# EnsembleNine.net
KiCad netlist of a schematic drawn in EAGLE
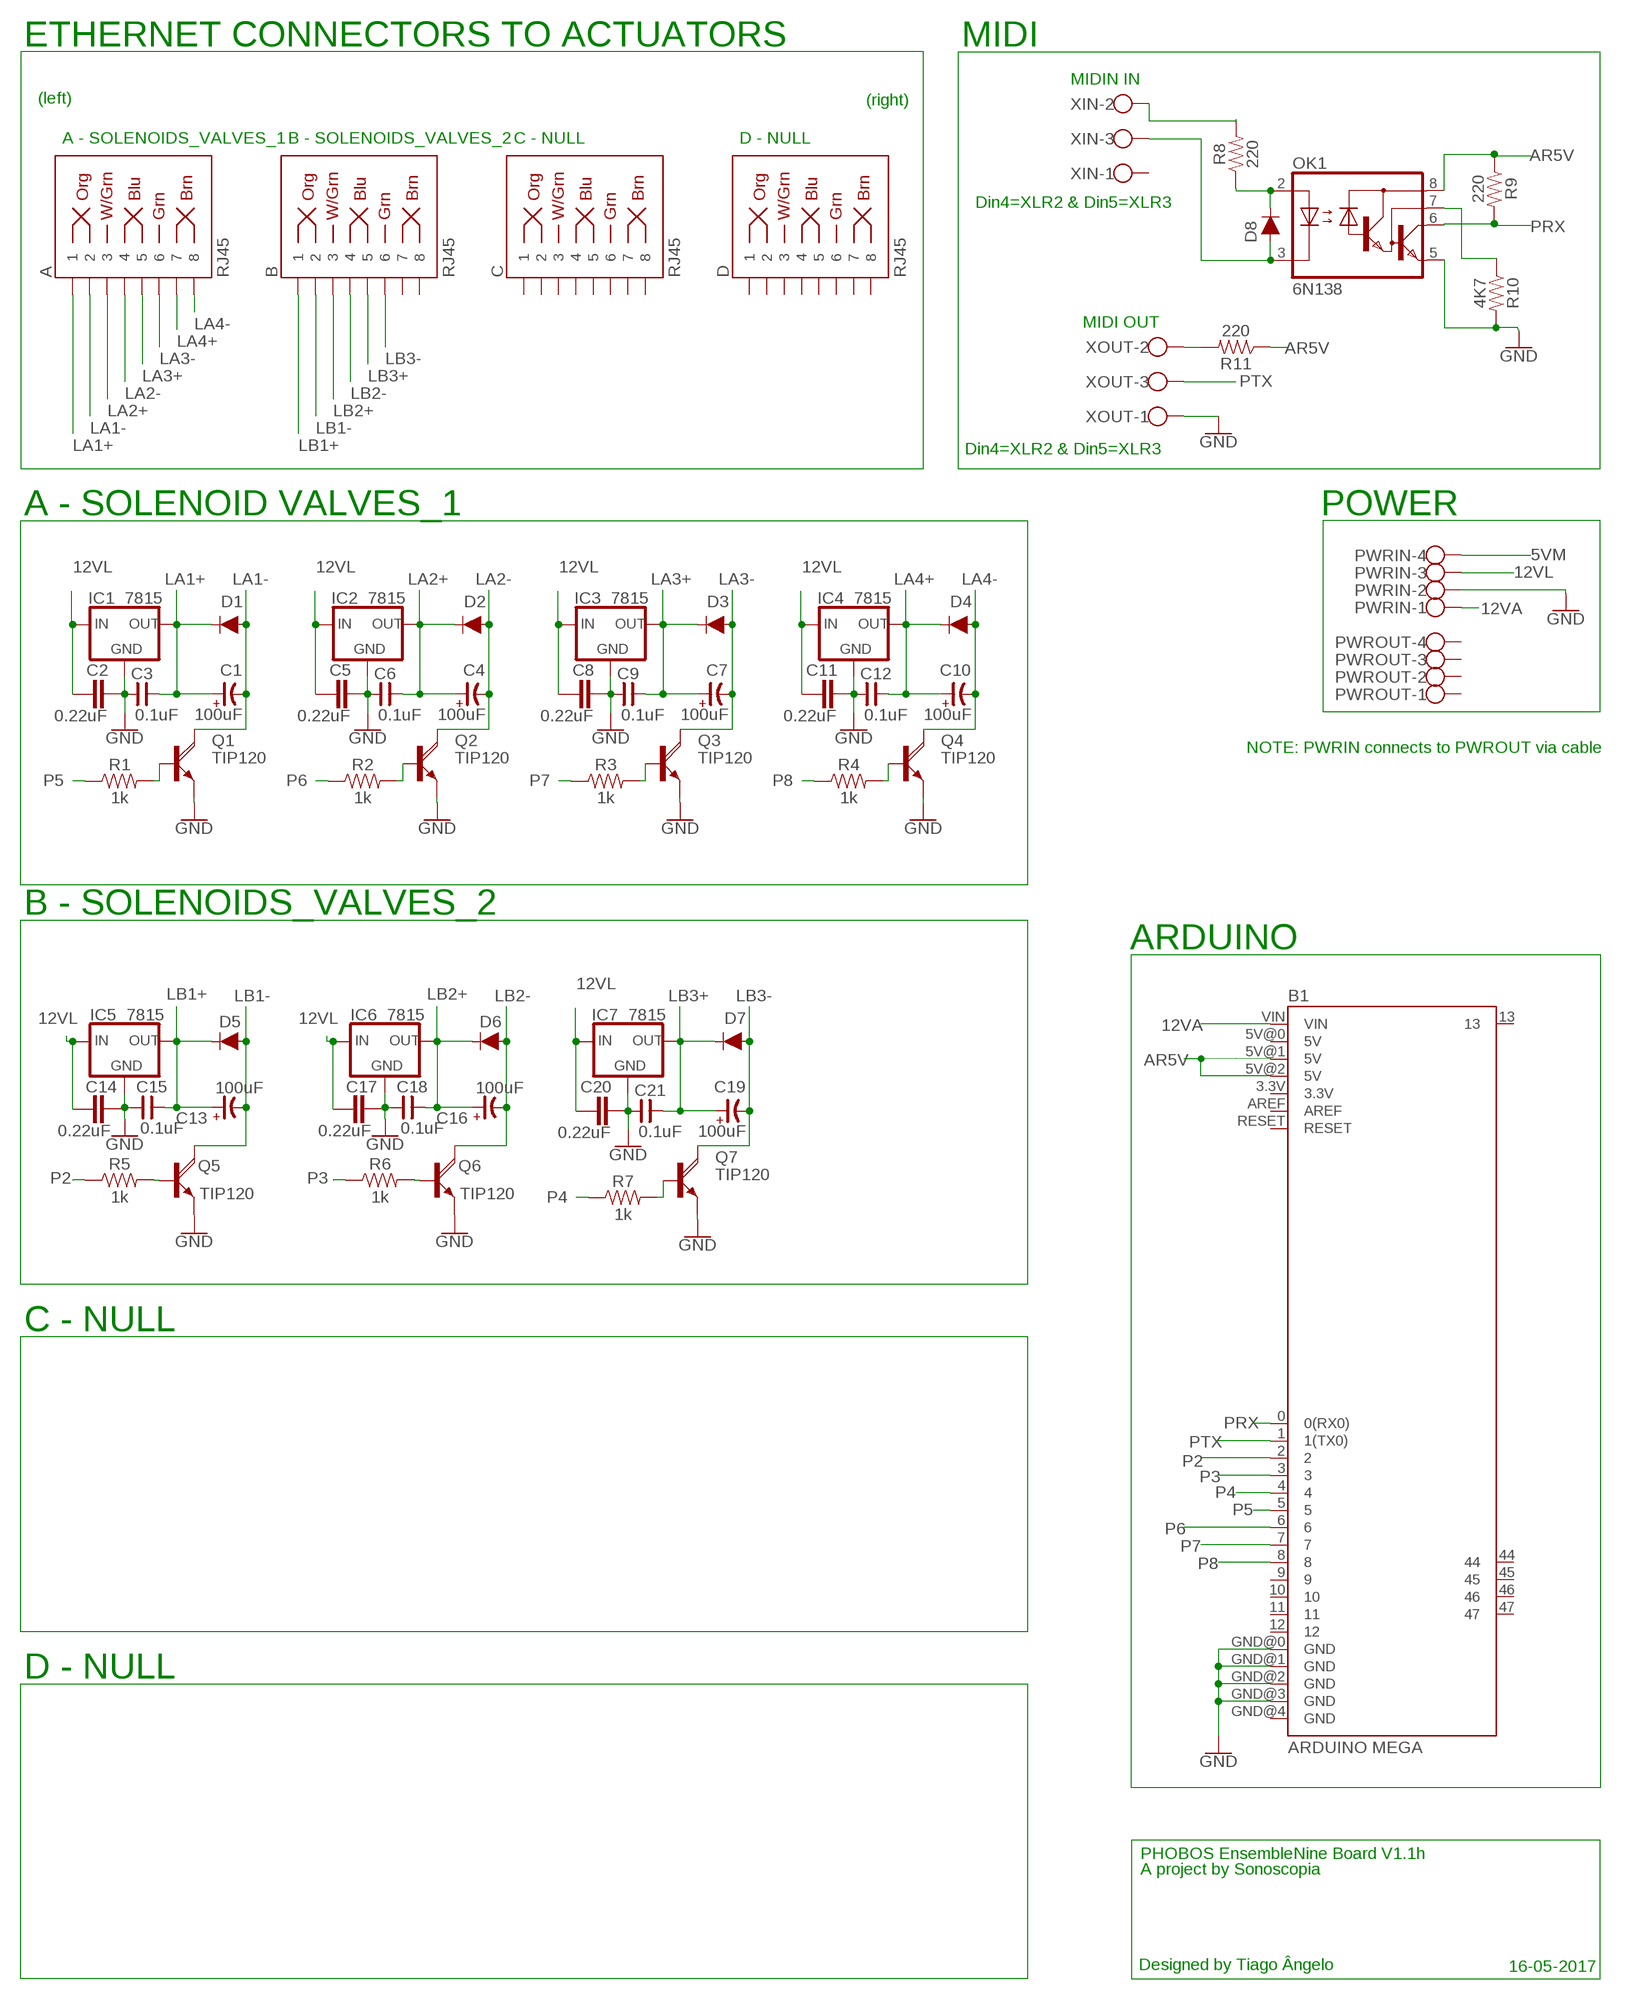
[diagram p0: schematic, sheet 1]

(export (version "E")
  (design (tool "Eeschema 10.0.6"))
  (components
    (comp (ref "A")
      (value "RJ45")
      (footprint "eagle-import:RJ45-8")
      (libsource (lib "eagle-import") (part "RJ45-8"))
    )
    (comp (ref "B")
      (value "RJ45")
      (footprint "eagle-import:RJ45-8")
      (libsource (lib "eagle-import") (part "RJ45-8"))
    )
    (comp (ref "B1")
      (value "ARDUINO MEGA")
      (footprint "eagle-import:ARDUINO_MEGA")
      (libsource (lib "eagle-import") (part "ARDUINO_MEGA_R3FULL"))
    )
    (comp (ref "C")
      (value "RJ45")
      (footprint "eagle-import:RJ45-8")
      (libsource (lib "eagle-import") (part "RJ45-8"))
    )
    (comp (ref "C1")
      (value "100uF")
      (footprint "eagle-import:CAP-MASTER_E-020X050")
      (libsource (lib "eagle-import") (part "CAP-MASTER_CP-E-020X050"))
    )
    (comp (ref "C2")
      (value "0.22uF")
      (footprint "eagle-import:C5B3")
      (libsource (lib "eagle-import") (part "C5/3"))
    )
    (comp (ref "C3")
      (value "0.1uF")
      (footprint "eagle-import:C025-050X025")
      (libsource (lib "eagle-import") (part "CNP-C025-050X025"))
    )
    (comp (ref "C4")
      (value "100uF")
      (footprint "eagle-import:CAP-MASTER_E-020X050")
      (libsource (lib "eagle-import") (part "CAP-MASTER_CP-E-020X050"))
    )
    (comp (ref "C5")
      (value "0.22uF")
      (footprint "eagle-import:C5B3")
      (libsource (lib "eagle-import") (part "C5/3"))
    )
    (comp (ref "C6")
      (value "0.1uF")
      (footprint "eagle-import:C025-050X025")
      (libsource (lib "eagle-import") (part "CNP-C025-050X025"))
    )
    (comp (ref "C7")
      (value "100uF")
      (footprint "eagle-import:CAP-MASTER_E-020X050")
      (libsource (lib "eagle-import") (part "CAP-MASTER_CP-E-020X050"))
    )
    (comp (ref "C8")
      (value "0.22uF")
      (footprint "eagle-import:C5B3")
      (libsource (lib "eagle-import") (part "C5/3"))
    )
    (comp (ref "C9")
      (value "0.1uF")
      (footprint "eagle-import:C025-050X025")
      (libsource (lib "eagle-import") (part "CNP-C025-050X025"))
    )
    (comp (ref "C10")
      (value "100uF")
      (footprint "eagle-import:CAP-MASTER_E-020X050")
      (libsource (lib "eagle-import") (part "CAP-MASTER_CP-E-020X050"))
    )
    (comp (ref "C11")
      (value "0.22uF")
      (footprint "eagle-import:C5B3")
      (libsource (lib "eagle-import") (part "C5/3"))
    )
    (comp (ref "C12")
      (value "0.1uF")
      (footprint "eagle-import:C025-050X025")
      (libsource (lib "eagle-import") (part "CNP-C025-050X025"))
    )
    (comp (ref "C13")
      (value "100uF")
      (footprint "eagle-import:E-020X050")
      (libsource (lib "eagle-import") (part "CP-E-020X050"))
    )
    (comp (ref "C14")
      (value "0.22uF")
      (footprint "eagle-import:C5B3")
      (libsource (lib "eagle-import") (part "C5/3"))
    )
    (comp (ref "C15")
      (value "0.1uF")
      (footprint "eagle-import:C025-050X025")
      (libsource (lib "eagle-import") (part "CNP-C025-050X025"))
    )
    (comp (ref "C16")
      (value "100uF")
      (footprint "eagle-import:E-020X050")
      (libsource (lib "eagle-import") (part "CP-E-020X050"))
    )
    (comp (ref "C17")
      (value "0.22uF")
      (footprint "eagle-import:C5B3")
      (libsource (lib "eagle-import") (part "C5/3"))
    )
    (comp (ref "C18")
      (value "0.1uF")
      (footprint "eagle-import:C025-050X025")
      (libsource (lib "eagle-import") (part "CNP-C025-050X025"))
    )
    (comp (ref "C19")
      (value "100uF")
      (footprint "eagle-import:CAP-MASTER_E-020X050")
      (libsource (lib "eagle-import") (part "CAP-MASTER_CP-E-020X050"))
    )
    (comp (ref "C20")
      (value "0.22uF")
      (footprint "eagle-import:C5B3")
      (libsource (lib "eagle-import") (part "C5/3"))
    )
    (comp (ref "C21")
      (value "0.1uF")
      (footprint "eagle-import:C025-050X025")
      (libsource (lib "eagle-import") (part "CNP-C025-050X025"))
    )
    (comp (ref "D")
      (value "RJ45")
      (footprint "eagle-import:RJ45-8")
      (libsource (lib "eagle-import") (part "RJ45-8"))
    )
    (comp (ref "D1")
      (value "1A/50V/1.1V")
      (footprint "eagle-import:DIODE-1N4001-KIT")
      (libsource (lib "eagle-import") (part "DIODE-KIT2"))
    )
    (comp (ref "D2")
      (value "1A/50V/1.1V")
      (footprint "eagle-import:DIODE-1N4001-KIT")
      (libsource (lib "eagle-import") (part "DIODE-KIT2"))
    )
    (comp (ref "D3")
      (value "1A/50V/1.1V")
      (footprint "eagle-import:DIODE-1N4001-KIT")
      (libsource (lib "eagle-import") (part "DIODE-KIT2"))
    )
    (comp (ref "D4")
      (value "1A/50V/1.1V")
      (footprint "eagle-import:DIODE-1N4001-KIT")
      (libsource (lib "eagle-import") (part "DIODE-KIT2"))
    )
    (comp (ref "D5")
      (value "1A/50V/1.1V")
      (footprint "eagle-import:DIODE-1N4001-KIT")
      (libsource (lib "eagle-import") (part "DIODE-KIT2"))
    )
    (comp (ref "D6")
      (value "1A/50V/1.1V")
      (footprint "eagle-import:DIODE-1N4001-KIT")
      (libsource (lib "eagle-import") (part "DIODE-KIT2"))
    )
    (comp (ref "D7")
      (value "1A/50V/1.1V")
      (footprint "eagle-import:DIODE-1N4001-KIT")
      (libsource (lib "eagle-import") (part "DIODE-KIT2"))
    )
    (comp (ref "D8")
      (value "200mA/100V/1V")
      (footprint "eagle-import:DIODE-1N4148")
      (libsource (lib "eagle-import") (part "DIODE-1N4148"))
    )
    (comp (ref "IC1")
      (value "7815")
      (footprint "eagle-import:78XXS")
      (libsource (lib "eagle-import") (part "78XXS"))
    )
    (comp (ref "IC2")
      (value "7815")
      (footprint "eagle-import:78XXS")
      (libsource (lib "eagle-import") (part "78XXS"))
    )
    (comp (ref "IC3")
      (value "7815")
      (footprint "eagle-import:78XXS")
      (libsource (lib "eagle-import") (part "78XXS"))
    )
    (comp (ref "IC4")
      (value "7815")
      (footprint "eagle-import:78XXS")
      (libsource (lib "eagle-import") (part "78XXS"))
    )
    (comp (ref "IC5")
      (value "7815")
      (footprint "eagle-import:78XXS")
      (libsource (lib "eagle-import") (part "78XXS"))
    )
    (comp (ref "IC6")
      (value "7815")
      (footprint "eagle-import:78XXS")
      (libsource (lib "eagle-import") (part "78XXS"))
    )
    (comp (ref "IC7")
      (value "7815")
      (footprint "eagle-import:78XXS")
      (libsource (lib "eagle-import") (part "78XXS"))
    )
    (comp (ref "OK1")
      (value "6N138")
      (footprint "eagle-import:DIL08")
      (fields (field (name "MF") "VISHAY/TELEFUNKEN"))
      (libsource (lib "eagle-import") (part "6N138"))
    )
    (comp (ref "PWRIN")
      (value "W237-4")
      (footprint "eagle-import:W237-4")
      (libsource (lib "eagle-import") (part "W237-4"))
    )
    (comp (ref "PWROUT")
      (value "W237-4")
      (footprint "eagle-import:W237-4")
      (libsource (lib "eagle-import") (part "W237-4"))
    )
    (comp (ref "Q1")
      (value "TIP120")
      (footprint "eagle-import:ROCKETFARM_TO220AV")
      (libsource (lib "eagle-import") (part "ROCKETFARM_TIP120V"))
    )
    (comp (ref "Q2")
      (value "TIP120")
      (footprint "eagle-import:ROCKETFARM_TO220AV")
      (libsource (lib "eagle-import") (part "ROCKETFARM_TIP120V"))
    )
    (comp (ref "Q3")
      (value "TIP120")
      (footprint "eagle-import:ROCKETFARM_TO220AV")
      (libsource (lib "eagle-import") (part "ROCKETFARM_TIP120V"))
    )
    (comp (ref "Q4")
      (value "TIP120")
      (footprint "eagle-import:ROCKETFARM_TO220AV")
      (libsource (lib "eagle-import") (part "ROCKETFARM_TIP120V"))
    )
    (comp (ref "Q5")
      (value "TIP120")
      (footprint "eagle-import:TO220AV")
      (libsource (lib "eagle-import") (part "TIP120V"))
    )
    (comp (ref "Q6")
      (value "TIP120")
      (footprint "eagle-import:TO220AV")
      (libsource (lib "eagle-import") (part "TIP120V"))
    )
    (comp (ref "Q7")
      (value "TIP120")
      (footprint "eagle-import:ROCKETFARM_TO220AV")
      (libsource (lib "eagle-import") (part "ROCKETFARM_TIP120V"))
    )
    (comp (ref "R1")
      (value "1k")
      (footprint "eagle-import:AXIAL-0.1")
      (libsource (lib "eagle-import") (part "1KOHM-VERT-1/4W-1%"))
    )
    (comp (ref "R2")
      (value "1k")
      (footprint "eagle-import:AXIAL-0.1")
      (libsource (lib "eagle-import") (part "1KOHM-VERT-1/4W-1%"))
    )
    (comp (ref "R3")
      (value "1k")
      (footprint "eagle-import:AXIAL-0.1")
      (libsource (lib "eagle-import") (part "1KOHM-VERT-1/4W-1%"))
    )
    (comp (ref "R4")
      (value "1k")
      (footprint "eagle-import:AXIAL-0.1")
      (libsource (lib "eagle-import") (part "1KOHM-VERT-1/4W-1%"))
    )
    (comp (ref "R5")
      (value "1k")
      (footprint "eagle-import:AXIAL-0.1")
      (libsource (lib "eagle-import") (part "1KOHM-VERT-1/4W-1%"))
    )
    (comp (ref "R6")
      (value "1k")
      (footprint "eagle-import:AXIAL-0.1")
      (libsource (lib "eagle-import") (part "1KOHM-VERT-1/4W-1%"))
    )
    (comp (ref "R7")
      (value "1k")
      (footprint "eagle-import:AXIAL-0.1")
      (libsource (lib "eagle-import") (part "1KOHM-VERT-1/4W-1%"))
    )
    (comp (ref "R8")
      (value "220")
      (footprint "eagle-import:AXIAL-0.3")
      (libsource (lib "eagle-import") (part "1KOHM-HORIZ-1/4W-5%"))
    )
    (comp (ref "R9")
      (value "220")
      (footprint "eagle-import:AXIAL-0.3")
      (libsource (lib "eagle-import") (part "1KOHM-HORIZ-1/4W-5%"))
    )
    (comp (ref "R10")
      (value "4K7")
      (footprint "eagle-import:AXIAL-0.3")
      (libsource (lib "eagle-import") (part "1KOHM-HORIZ-1/4W-5%"))
    )
    (comp (ref "R11")
      (value "220")
      (footprint "eagle-import:AXIAL-0.3")
      (libsource (lib "eagle-import") (part "1KOHM-HORIZ-1/4W-5%"))
    )
    (comp (ref "XIN")
      (value "W237-103")
      (footprint "eagle-import:W237-103")
      (fields (field (name "MPN") "237-103"))
      (libsource (lib "eagle-import") (part "W237-103"))
    )
    (comp (ref "XOUT")
      (value "W237-103")
      (footprint "eagle-import:W237-103")
      (fields (field (name "MPN") "237-103"))
      (libsource (lib "eagle-import") (part "W237-103"))
    )
  )
  (nets
    (net (code "1") (name "/5VM") (class "Default")
      (node (ref "PWRIN") (pin "4") (pinfunction "KL_4") (pintype "passive"))
    )
    (net (code "2") (name "/12VA") (class "Default")
      (node (ref "B1") (pin "VIN") (pinfunction "VIN_VIN") (pintype "bidirectional"))
      (node (ref "PWRIN") (pin "1") (pinfunction "KL_1") (pintype "passive"))
    )
    (net (code "3") (name "/12VL") (class "Default")
      (node (ref "C11") (pin "1") (pinfunction "1_1") (pintype "passive"))
      (node (ref "C14") (pin "1") (pinfunction "1_1") (pintype "passive"))
      (node (ref "C17") (pin "1") (pinfunction "1_1") (pintype "passive"))
      (node (ref "C2") (pin "1") (pinfunction "1_1") (pintype "passive"))
      (node (ref "C20") (pin "1") (pinfunction "1_1") (pintype "passive"))
      (node (ref "C5") (pin "1") (pinfunction "1_1") (pintype "passive"))
      (node (ref "C8") (pin "1") (pinfunction "1_1") (pintype "passive"))
      (node (ref "IC1") (pin "IN") (pinfunction "IN_IN") (pintype "input"))
      (node (ref "IC2") (pin "IN") (pinfunction "IN_IN") (pintype "input"))
      (node (ref "IC3") (pin "IN") (pinfunction "IN_IN") (pintype "input"))
      (node (ref "IC4") (pin "IN") (pinfunction "IN_IN") (pintype "input"))
      (node (ref "IC5") (pin "IN") (pinfunction "IN_IN") (pintype "input"))
      (node (ref "IC6") (pin "IN") (pinfunction "IN_IN") (pintype "input"))
      (node (ref "IC7") (pin "IN") (pinfunction "IN_IN") (pintype "input"))
      (node (ref "PWRIN") (pin "3") (pinfunction "KL_3") (pintype "passive"))
    )
    (net (code "4") (name "/AR5V") (class "Default")
      (node (ref "B1") (pin "5V@1") (pinfunction "5V_5V@1") (pintype "bidirectional"))
      (node (ref "B1") (pin "5V@2") (pinfunction "5V_5V@2") (pintype "bidirectional"))
      (node (ref "OK1") (pin "8") (pinfunction "VCC_8") (pintype "passive"))
      (node (ref "R11") (pin "P$1") (pinfunction "1_P$1") (pintype "passive"))
      (node (ref "R9") (pin "P$1") (pinfunction "1_P$1") (pintype "passive"))
    )
    (net (code "5") (name "/LA1+") (class "Default")
      (node (ref "A") (pin "1") (pinfunction "1_1") (pintype "bidirectional"))
      (node (ref "C1") (pin "+") (pinfunction "+_+") (pintype "passive"))
      (node (ref "C3") (pin "2") (pinfunction "2_2") (pintype "passive"))
      (node (ref "D1") (pin "C") (pinfunction "C_C") (pintype "passive"))
      (node (ref "IC1") (pin "OUT") (pinfunction "OUT_OUT") (pintype "passive"))
    )
    (net (code "6") (name "/LA1-") (class "Default")
      (node (ref "A") (pin "2") (pinfunction "2_2") (pintype "bidirectional"))
      (node (ref "C1") (pin "-") (pinfunction "-_-") (pintype "passive"))
      (node (ref "D1") (pin "A") (pinfunction "A_A") (pintype "passive"))
      (node (ref "Q1") (pin "C") (pinfunction "C_C") (pintype "passive"))
    )
    (net (code "7") (name "/LA2+") (class "Default")
      (node (ref "A") (pin "3") (pinfunction "3_3") (pintype "bidirectional"))
      (node (ref "C4") (pin "+") (pinfunction "+_+") (pintype "passive"))
      (node (ref "C6") (pin "2") (pinfunction "2_2") (pintype "passive"))
      (node (ref "D2") (pin "C") (pinfunction "C_C") (pintype "passive"))
      (node (ref "IC2") (pin "OUT") (pinfunction "OUT_OUT") (pintype "passive"))
    )
    (net (code "8") (name "/LA2-") (class "Default")
      (node (ref "A") (pin "4") (pinfunction "4_4") (pintype "bidirectional"))
      (node (ref "C4") (pin "-") (pinfunction "-_-") (pintype "passive"))
      (node (ref "D2") (pin "A") (pinfunction "A_A") (pintype "passive"))
      (node (ref "Q2") (pin "C") (pinfunction "C_C") (pintype "passive"))
    )
    (net (code "9") (name "/LA3+") (class "Default")
      (node (ref "A") (pin "5") (pinfunction "5_5") (pintype "bidirectional"))
      (node (ref "C7") (pin "+") (pinfunction "+_+") (pintype "passive"))
      (node (ref "C9") (pin "2") (pinfunction "2_2") (pintype "passive"))
      (node (ref "D3") (pin "C") (pinfunction "C_C") (pintype "passive"))
      (node (ref "IC3") (pin "OUT") (pinfunction "OUT_OUT") (pintype "passive"))
    )
    (net (code "10") (name "/LA3-") (class "Default")
      (node (ref "A") (pin "6") (pinfunction "6_6") (pintype "bidirectional"))
      (node (ref "C7") (pin "-") (pinfunction "-_-") (pintype "passive"))
      (node (ref "D3") (pin "A") (pinfunction "A_A") (pintype "passive"))
      (node (ref "Q3") (pin "C") (pinfunction "C_C") (pintype "passive"))
    )
    (net (code "11") (name "/LA4+") (class "Default")
      (node (ref "A") (pin "7") (pinfunction "7_7") (pintype "bidirectional"))
      (node (ref "C10") (pin "+") (pinfunction "+_+") (pintype "passive"))
      (node (ref "C12") (pin "2") (pinfunction "2_2") (pintype "passive"))
      (node (ref "D4") (pin "C") (pinfunction "C_C") (pintype "passive"))
      (node (ref "IC4") (pin "OUT") (pinfunction "OUT_OUT") (pintype "passive"))
    )
    (net (code "12") (name "/LA4-") (class "Default")
      (node (ref "A") (pin "8") (pinfunction "8_8") (pintype "bidirectional"))
      (node (ref "C10") (pin "-") (pinfunction "-_-") (pintype "passive"))
      (node (ref "D4") (pin "A") (pinfunction "A_A") (pintype "passive"))
      (node (ref "Q4") (pin "C") (pinfunction "C_C") (pintype "passive"))
    )
    (net (code "13") (name "/LB1+") (class "Default")
      (node (ref "B") (pin "1") (pinfunction "1_1") (pintype "bidirectional"))
      (node (ref "C13") (pin "+") (pinfunction "+_+") (pintype "passive"))
      (node (ref "C15") (pin "2") (pinfunction "2_2") (pintype "passive"))
      (node (ref "D5") (pin "C") (pinfunction "C_C") (pintype "passive"))
      (node (ref "IC5") (pin "OUT") (pinfunction "OUT_OUT") (pintype "passive"))
    )
    (net (code "14") (name "/LB1-") (class "Default")
      (node (ref "B") (pin "2") (pinfunction "2_2") (pintype "bidirectional"))
      (node (ref "C13") (pin "-") (pinfunction "-_-") (pintype "passive"))
      (node (ref "D5") (pin "A") (pinfunction "A_A") (pintype "passive"))
      (node (ref "Q5") (pin "C") (pinfunction "C_C") (pintype "passive"))
    )
    (net (code "15") (name "/LB2+") (class "Default")
      (node (ref "B") (pin "3") (pinfunction "3_3") (pintype "bidirectional"))
      (node (ref "C16") (pin "+") (pinfunction "+_+") (pintype "passive"))
      (node (ref "C18") (pin "2") (pinfunction "2_2") (pintype "passive"))
      (node (ref "D6") (pin "C") (pinfunction "C_C") (pintype "passive"))
      (node (ref "IC6") (pin "OUT") (pinfunction "OUT_OUT") (pintype "passive"))
    )
    (net (code "16") (name "/LB2-") (class "Default")
      (node (ref "B") (pin "4") (pinfunction "4_4") (pintype "bidirectional"))
      (node (ref "C16") (pin "-") (pinfunction "-_-") (pintype "passive"))
      (node (ref "D6") (pin "A") (pinfunction "A_A") (pintype "passive"))
      (node (ref "Q6") (pin "C") (pinfunction "C_C") (pintype "passive"))
    )
    (net (code "17") (name "/LB3+") (class "Default")
      (node (ref "B") (pin "5") (pinfunction "5_5") (pintype "bidirectional"))
      (node (ref "C19") (pin "+") (pinfunction "+_+") (pintype "passive"))
      (node (ref "C21") (pin "2") (pinfunction "2_2") (pintype "passive"))
      (node (ref "D7") (pin "C") (pinfunction "C_C") (pintype "passive"))
      (node (ref "IC7") (pin "OUT") (pinfunction "OUT_OUT") (pintype "passive"))
    )
    (net (code "18") (name "/LB3-") (class "Default")
      (node (ref "B") (pin "6") (pinfunction "6_6") (pintype "bidirectional"))
      (node (ref "C19") (pin "-") (pinfunction "-_-") (pintype "passive"))
      (node (ref "D7") (pin "A") (pinfunction "A_A") (pintype "passive"))
      (node (ref "Q7") (pin "C") (pinfunction "C_C") (pintype "passive"))
    )
    (net (code "19") (name "/P2") (class "Default")
      (node (ref "B1") (pin "2") (pinfunction "2_2") (pintype "bidirectional"))
      (node (ref "R5") (pin "P$1") (pinfunction "1_P$1") (pintype "passive"))
    )
    (net (code "20") (name "/P3") (class "Default")
      (node (ref "B1") (pin "3") (pinfunction "3_3") (pintype "bidirectional"))
      (node (ref "R6") (pin "P$1") (pinfunction "1_P$1") (pintype "passive"))
    )
    (net (code "21") (name "/P4") (class "Default")
      (node (ref "B1") (pin "4") (pinfunction "4_4") (pintype "bidirectional"))
      (node (ref "R7") (pin "P$1") (pinfunction "1_P$1") (pintype "passive"))
    )
    (net (code "22") (name "/P5") (class "Default")
      (node (ref "B1") (pin "5") (pinfunction "5_5") (pintype "bidirectional"))
      (node (ref "R1") (pin "P$1") (pinfunction "1_P$1") (pintype "passive"))
    )
    (net (code "23") (name "/P6") (class "Default")
      (node (ref "B1") (pin "6") (pinfunction "6_6") (pintype "bidirectional"))
      (node (ref "R2") (pin "P$1") (pinfunction "1_P$1") (pintype "passive"))
    )
    (net (code "24") (name "/P7") (class "Default")
      (node (ref "B1") (pin "7") (pinfunction "7_7") (pintype "bidirectional"))
      (node (ref "R3") (pin "P$1") (pinfunction "1_P$1") (pintype "passive"))
    )
    (net (code "25") (name "/P8") (class "Default")
      (node (ref "B1") (pin "8") (pinfunction "8_8") (pintype "bidirectional"))
      (node (ref "R4") (pin "P$1") (pinfunction "1_P$1") (pintype "passive"))
    )
    (net (code "26") (name "/PRX") (class "Default")
      (node (ref "B1") (pin "0") (pinfunction "0(RX0)_0") (pintype "bidirectional"))
      (node (ref "OK1") (pin "6") (pinfunction "VO_6") (pintype "passive"))
      (node (ref "R9") (pin "P$2") (pinfunction "2_P$2") (pintype "passive"))
    )
    (net (code "27") (name "/PTX") (class "Default")
      (node (ref "B1") (pin "1") (pinfunction "1(TX0)_1") (pintype "bidirectional"))
      (node (ref "XOUT") (pin "3") (pinfunction "KL_3") (pintype "passive"))
    )
    (net (code "28") (name "GND") (class "Default")
      (node (ref "B1") (pin "GND@0") (pinfunction "GND_GND@0") (pintype "bidirectional"))
      (node (ref "B1") (pin "GND@1") (pinfunction "GND_GND@1") (pintype "bidirectional"))
      (node (ref "B1") (pin "GND@2") (pinfunction "GND_GND@2") (pintype "bidirectional"))
      (node (ref "B1") (pin "GND@3") (pinfunction "GND_GND@3") (pintype "bidirectional"))
      (node (ref "C11") (pin "2") (pinfunction "2_2") (pintype "passive"))
      (node (ref "C12") (pin "1") (pinfunction "1_1") (pintype "passive"))
      (node (ref "C14") (pin "2") (pinfunction "2_2") (pintype "passive"))
      (node (ref "C15") (pin "1") (pinfunction "1_1") (pintype "passive"))
      (node (ref "C17") (pin "2") (pinfunction "2_2") (pintype "passive"))
      (node (ref "C18") (pin "1") (pinfunction "1_1") (pintype "passive"))
      (node (ref "C2") (pin "2") (pinfunction "2_2") (pintype "passive"))
      (node (ref "C20") (pin "2") (pinfunction "2_2") (pintype "passive"))
      (node (ref "C21") (pin "1") (pinfunction "1_1") (pintype "passive"))
      (node (ref "C3") (pin "1") (pinfunction "1_1") (pintype "passive"))
      (node (ref "C5") (pin "2") (pinfunction "2_2") (pintype "passive"))
      (node (ref "C6") (pin "1") (pinfunction "1_1") (pintype "passive"))
      (node (ref "C8") (pin "2") (pinfunction "2_2") (pintype "passive"))
      (node (ref "C9") (pin "1") (pinfunction "1_1") (pintype "passive"))
      (node (ref "IC1") (pin "GND") (pinfunction "GND_GND") (pintype "input"))
      (node (ref "IC2") (pin "GND") (pinfunction "GND_GND") (pintype "input"))
      (node (ref "IC3") (pin "GND") (pinfunction "GND_GND") (pintype "input"))
      (node (ref "IC4") (pin "GND") (pinfunction "GND_GND") (pintype "input"))
      (node (ref "IC5") (pin "GND") (pinfunction "GND_GND") (pintype "input"))
      (node (ref "IC6") (pin "GND") (pinfunction "GND_GND") (pintype "input"))
      (node (ref "IC7") (pin "GND") (pinfunction "GND_GND") (pintype "input"))
      (node (ref "OK1") (pin "5") (pinfunction "GND_5") (pintype "passive"))
      (node (ref "PWRIN") (pin "2") (pinfunction "KL_2") (pintype "passive"))
      (node (ref "Q1") (pin "E") (pinfunction "E_E") (pintype "passive"))
      (node (ref "Q2") (pin "E") (pinfunction "E_E") (pintype "passive"))
      (node (ref "Q3") (pin "E") (pinfunction "E_E") (pintype "passive"))
      (node (ref "Q4") (pin "E") (pinfunction "E_E") (pintype "passive"))
      (node (ref "Q5") (pin "E") (pinfunction "E_E") (pintype "passive"))
      (node (ref "Q6") (pin "E") (pinfunction "E_E") (pintype "passive"))
      (node (ref "Q7") (pin "E") (pinfunction "E_E") (pintype "passive"))
      (node (ref "R10") (pin "P$2") (pinfunction "2_P$2") (pintype "passive"))
      (node (ref "XOUT") (pin "1") (pinfunction "KL_1") (pintype "passive"))
    )
    (net (code "29") (name "Net-(OK1-A)") (class "Default")
      (node (ref "D8") (pin "C") (pinfunction "C_C") (pintype "passive"))
      (node (ref "OK1") (pin "2") (pinfunction "A_2") (pintype "passive"))
      (node (ref "R8") (pin "P$1") (pinfunction "1_P$1") (pintype "passive"))
    )
    (net (code "30") (name "Net-(OK1-C)") (class "Default")
      (node (ref "D8") (pin "A") (pinfunction "A_A") (pintype "passive"))
      (node (ref "OK1") (pin "3") (pinfunction "C_3") (pintype "passive"))
      (node (ref "XIN") (pin "3") (pinfunction "KL_3") (pintype "passive"))
    )
    (net (code "31") (name "Net-(OK1-VB)") (class "Default")
      (node (ref "OK1") (pin "7") (pinfunction "VB_7") (pintype "passive"))
      (node (ref "R10") (pin "P$1") (pinfunction "1_P$1") (pintype "passive"))
    )
    (net (code "32") (name "Net-(R1-2)") (class "Default")
      (node (ref "Q1") (pin "B") (pinfunction "B_B") (pintype "passive"))
      (node (ref "R1") (pin "P$2") (pinfunction "2_P$2") (pintype "passive"))
    )
    (net (code "33") (name "Net-(R2-2)") (class "Default")
      (node (ref "Q2") (pin "B") (pinfunction "B_B") (pintype "passive"))
      (node (ref "R2") (pin "P$2") (pinfunction "2_P$2") (pintype "passive"))
    )
    (net (code "34") (name "Net-(R3-2)") (class "Default")
      (node (ref "Q3") (pin "B") (pinfunction "B_B") (pintype "passive"))
      (node (ref "R3") (pin "P$2") (pinfunction "2_P$2") (pintype "passive"))
    )
    (net (code "35") (name "Net-(R4-2)") (class "Default")
      (node (ref "Q4") (pin "B") (pinfunction "B_B") (pintype "passive"))
      (node (ref "R4") (pin "P$2") (pinfunction "2_P$2") (pintype "passive"))
    )
    (net (code "36") (name "Net-(R5-2)") (class "Default")
      (node (ref "Q5") (pin "B") (pinfunction "B_B") (pintype "passive"))
      (node (ref "R5") (pin "P$2") (pinfunction "2_P$2") (pintype "passive"))
    )
    (net (code "37") (name "Net-(R6-2)") (class "Default")
      (node (ref "Q6") (pin "B") (pinfunction "B_B") (pintype "passive"))
      (node (ref "R6") (pin "P$2") (pinfunction "2_P$2") (pintype "passive"))
    )
    (net (code "38") (name "Net-(R7-2)") (class "Default")
      (node (ref "Q7") (pin "B") (pinfunction "B_B") (pintype "passive"))
      (node (ref "R7") (pin "P$2") (pinfunction "2_P$2") (pintype "passive"))
    )
    (net (code "39") (name "Net-(R8-2)") (class "Default")
      (node (ref "R8") (pin "P$2") (pinfunction "2_P$2") (pintype "passive"))
      (node (ref "XIN") (pin "2") (pinfunction "KL_2") (pintype "passive"))
    )
    (net (code "40") (name "Net-(R11-2)") (class "Default")
      (node (ref "R11") (pin "P$2") (pinfunction "2_P$2") (pintype "passive"))
      (node (ref "XOUT") (pin "2") (pinfunction "KL_2") (pintype "passive"))
    )
    (net (code "41") (name "unconnected-(B-Pad7)") (class "Default")
      (node (ref "B") (pin "7") (pinfunction "7_7") (pintype "bidirectional"))
    )
    (net (code "42") (name "unconnected-(B-Pad8)") (class "Default")
      (node (ref "B") (pin "8") (pinfunction "8_8") (pintype "bidirectional"))
    )
    (net (code "43") (name "unconnected-(B1-5V-Pad5V@0)") (class "Default")
      (node (ref "B1") (pin "5V@0") (pinfunction "5V_5V@0") (pintype "bidirectional"))
    )
    (net (code "44") (name "unconnected-(B1-GND-PadGND@4)") (class "Default")
      (node (ref "B1") (pin "GND@4") (pinfunction "GND_GND@4") (pintype "bidirectional"))
    )
    (net (code "45") (name "unconnected-(B1-Pad3.3V)") (class "Default")
      (node (ref "B1") (pin "3.3V") (pinfunction "3.3V_3.3V") (pintype "bidirectional"))
    )
    (net (code "46") (name "unconnected-(B1-Pad9)") (class "Default")
      (node (ref "B1") (pin "9") (pinfunction "9_9") (pintype "bidirectional"))
    )
    (net (code "47") (name "unconnected-(B1-Pad10)") (class "Default")
      (node (ref "B1") (pin "10") (pinfunction "10_10") (pintype "bidirectional"))
    )
    (net (code "48") (name "unconnected-(B1-Pad11)") (class "Default")
      (node (ref "B1") (pin "11") (pinfunction "11_11") (pintype "bidirectional"))
    )
    (net (code "49") (name "unconnected-(B1-Pad12)") (class "Default")
      (node (ref "B1") (pin "12") (pinfunction "12_12") (pintype "bidirectional"))
    )
    (net (code "50") (name "unconnected-(B1-Pad13)") (class "Default")
      (node (ref "B1") (pin "13") (pinfunction "13_13") (pintype "bidirectional"))
    )
    (net (code "51") (name "unconnected-(B1-Pad44)") (class "Default")
      (node (ref "B1") (pin "44") (pinfunction "44_44") (pintype "bidirectional"))
    )
    (net (code "52") (name "unconnected-(B1-Pad45)") (class "Default")
      (node (ref "B1") (pin "45") (pinfunction "45_45") (pintype "bidirectional"))
    )
    (net (code "53") (name "unconnected-(B1-Pad46)") (class "Default")
      (node (ref "B1") (pin "46") (pinfunction "46_46") (pintype "bidirectional"))
    )
    (net (code "54") (name "unconnected-(B1-Pad47)") (class "Default")
      (node (ref "B1") (pin "47") (pinfunction "47_47") (pintype "bidirectional"))
    )
    (net (code "55") (name "unconnected-(B1-PadAREF)") (class "Default")
      (node (ref "B1") (pin "AREF") (pinfunction "AREF_AREF") (pintype "bidirectional"))
    )
    (net (code "56") (name "unconnected-(B1-PadRESET)") (class "Default")
      (node (ref "B1") (pin "RESET") (pinfunction "RESET_RESET") (pintype "bidirectional"))
    )
    (net (code "57") (name "unconnected-(C-Pad1)") (class "Default")
      (node (ref "C") (pin "1") (pinfunction "1_1") (pintype "bidirectional"))
    )
    (net (code "58") (name "unconnected-(C-Pad2)") (class "Default")
      (node (ref "C") (pin "2") (pinfunction "2_2") (pintype "bidirectional"))
    )
    (net (code "59") (name "unconnected-(C-Pad3)") (class "Default")
      (node (ref "C") (pin "3") (pinfunction "3_3") (pintype "bidirectional"))
    )
    (net (code "60") (name "unconnected-(C-Pad4)") (class "Default")
      (node (ref "C") (pin "4") (pinfunction "4_4") (pintype "bidirectional"))
    )
    (net (code "61") (name "unconnected-(C-Pad5)") (class "Default")
      (node (ref "C") (pin "5") (pinfunction "5_5") (pintype "bidirectional"))
    )
    (net (code "62") (name "unconnected-(C-Pad6)") (class "Default")
      (node (ref "C") (pin "6") (pinfunction "6_6") (pintype "bidirectional"))
    )
    (net (code "63") (name "unconnected-(C-Pad7)") (class "Default")
      (node (ref "C") (pin "7") (pinfunction "7_7") (pintype "bidirectional"))
    )
    (net (code "64") (name "unconnected-(C-Pad8)") (class "Default")
      (node (ref "C") (pin "8") (pinfunction "8_8") (pintype "bidirectional"))
    )
    (net (code "65") (name "unconnected-(D-Pad1)") (class "Default")
      (node (ref "D") (pin "1") (pinfunction "1_1") (pintype "bidirectional"))
    )
    (net (code "66") (name "unconnected-(D-Pad2)") (class "Default")
      (node (ref "D") (pin "2") (pinfunction "2_2") (pintype "bidirectional"))
    )
    (net (code "67") (name "unconnected-(D-Pad3)") (class "Default")
      (node (ref "D") (pin "3") (pinfunction "3_3") (pintype "bidirectional"))
    )
    (net (code "68") (name "unconnected-(D-Pad4)") (class "Default")
      (node (ref "D") (pin "4") (pinfunction "4_4") (pintype "bidirectional"))
    )
    (net (code "69") (name "unconnected-(D-Pad5)") (class "Default")
      (node (ref "D") (pin "5") (pinfunction "5_5") (pintype "bidirectional"))
    )
    (net (code "70") (name "unconnected-(D-Pad6)") (class "Default")
      (node (ref "D") (pin "6") (pinfunction "6_6") (pintype "bidirectional"))
    )
    (net (code "71") (name "unconnected-(D-Pad7)") (class "Default")
      (node (ref "D") (pin "7") (pinfunction "7_7") (pintype "bidirectional"))
    )
    (net (code "72") (name "unconnected-(D-Pad8)") (class "Default")
      (node (ref "D") (pin "8") (pinfunction "8_8") (pintype "bidirectional"))
    )
    (net (code "73") (name "unconnected-(PWROUTA-KL-Pad1)") (class "Default")
      (node (ref "PWROUT") (pin "1") (pinfunction "KL_1") (pintype "passive"))
    )
    (net (code "74") (name "unconnected-(PWROUTB-KL-Pad2)") (class "Default")
      (node (ref "PWROUT") (pin "2") (pinfunction "KL_2") (pintype "passive"))
    )
    (net (code "75") (name "unconnected-(PWROUTC-KL-Pad3)") (class "Default")
      (node (ref "PWROUT") (pin "3") (pinfunction "KL_3") (pintype "passive"))
    )
    (net (code "76") (name "unconnected-(PWROUTD-KL-Pad4)") (class "Default")
      (node (ref "PWROUT") (pin "4") (pinfunction "KL_4") (pintype "passive"))
    )
    (net (code "77") (name "unconnected-(XINA-KL-Pad1)") (class "Default")
      (node (ref "XIN") (pin "1") (pinfunction "KL_1") (pintype "passive"))
    )
  )
)
